# Top.net
KiCad netlist of a schematic drawn in Altium Designer
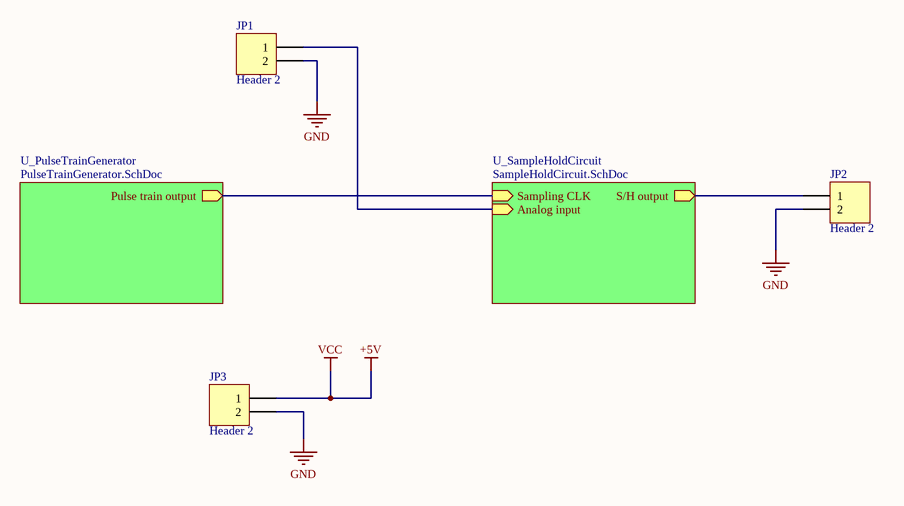
[diagram p0: Top.SchDoc]

(export (version "E")
  (design (tool "Eeschema 10.0.6"))
  (components
    (comp (ref "JP1")
      (value "Header 2")
      (footprint "HDR1X2")
      (description "Header, 2-Pin")
      (fields (field (name "PUBLISHER") "Altium Limited"))
      (libsource (lib "ECET231SCHLIB_Rev01") (part "Header 2"))
    )
    (comp (ref "JP2")
      (value "Header 2")
      (footprint "HDR1X2")
      (description "Header, 2-Pin")
      (fields (field (name "PUBLISHER") "Altium Limited"))
      (libsource (lib "") (part "Header 2_1"))
    )
    (comp (ref "JP3")
      (value "Header 2")
      (footprint "HDR1X2")
      (description "Header, 2-Pin")
      (fields (field (name "PUBLISHER") "Altium Limited"))
      (libsource (lib "ECET231SCHLIB_Rev01") (part "Header 2"))
    )
  )
  (nets
    (net (code "1") (name "+5V") (class "Default")
      (node (ref "JP3") (pin "1") (pinfunction "1_1") (pintype "passive"))
    )
    (net (code "2") (name "/Analog input") (class "Default")
      (node (ref "JP1") (pin "1") (pinfunction "1_1") (pintype "passive"))
    )
    (net (code "4") (name "/S{slash}H output") (class "Default")
      (node (ref "JP2") (pin "1") (pinfunction "1_1") (pintype "passive"))
    )
    (net (code "5") (name "GND") (class "Default")
      (node (ref "JP1") (pin "2") (pinfunction "2_2") (pintype "passive"))
      (node (ref "JP2") (pin "2") (pinfunction "2_2") (pintype "passive"))
      (node (ref "JP3") (pin "2") (pinfunction "2_2") (pintype "passive"))
    )
  )
)
